# MIDImike.net
KiCad netlist of a schematic drawn in EAGLE
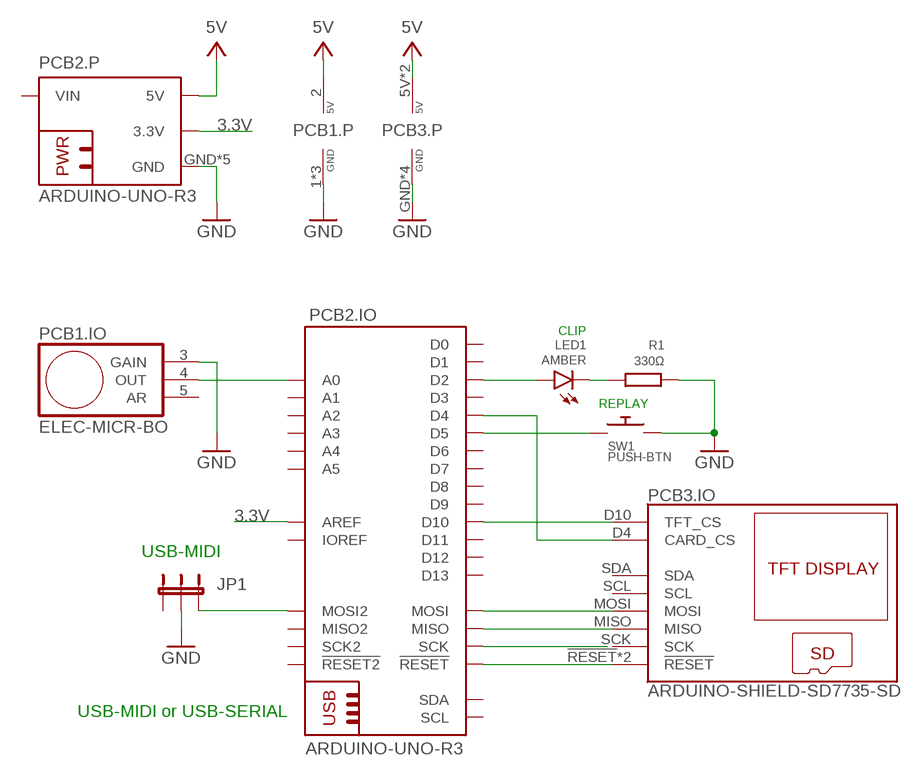
[diagram p0: schematic, sheet 1]

(export (version "E")
  (design (tool "Eeschema 10.0.6"))
  (components
    (comp (ref "JP1")
      (value "JP2E")
      (footprint "eagle-import:JP2")
      (libsource (lib "eagle-import") (part "JP2E"))
    )
    (comp (ref "LED1")
      (value "AMBER")
      (footprint "eagle-import:CHIPLED_0805")
      (libsource (lib "eagle-import") (part "LEDCHIPLED_0805"))
    )
    (comp (ref "PCB1")
      (value "ELEC-MICR-BO")
      (footprint "eagle-import:ELEC_MICR_BREAKOUT")
      (libsource (lib "eagle-import") (part "ELEC-MICR-BO"))
    )
    (comp (ref "PCB2")
      (value "ARDUINO-UNO-R3")
      (footprint "eagle-import:ARDUINO-UNO--R3")
      (libsource (lib "eagle-import") (part "ARDUINO-UNO-R3"))
    )
    (comp (ref "PCB3")
      (value "ARDUINO-SHIELD-SD7735-SD")
      (footprint "eagle-import:ARDIONO-SHIELD")
      (libsource (lib "eagle-import") (part "ARDUINO-SHIELD-SD7735-SD"))
    )
    (comp (ref "R1")
      (value "330Ω")
      (footprint "eagle-import:R0805")
      (fields (field (name "MANF") "Bourns"))
      (libsource (lib "eagle-import") (part "R-EU_R0805"))
    )
    (comp (ref "SW1")
      (value "PUSH-BTN")
      (footprint "eagle-import:TE_1-1825910-4")
      (fields
        (field (name "COMMENT") "1-1825910-4")
        (field (name "DIGI-KEY_PART_NUMBER") "450-1653-ND")
        (field (name "MF") "TE Connectivity")
      )
      (libsource (lib "eagle-import") (part "PUSH-BTN"))
    )
  )
  (nets
    (net (code "1") (name "/3.3V") (class "Default")
      (node (ref "PCB2") (pin "3.3V") (pinfunction "3.3V_3.3V") (pintype "power_in"))
      (node (ref "PCB2") (pin "AREF") (pinfunction "AREF_AREF") (pintype "bidirectional"))
    )
    (net (code "2") (name "/VIN") (class "Default")
      (node (ref "PCB2") (pin "VIN") (pinfunction "VIN_VIN") (pintype "power_in"))
    )
    (net (code "3") (name "5V") (class "Default")
      (node (ref "PCB1") (pin "2") (pinfunction "5V_2") (pintype "passive"))
      (node (ref "PCB2") (pin "5V") (pinfunction "5V_5V") (pintype "power_in"))
      (node (ref "PCB2") (pin "5V@1") (pinfunction "5V_5V@1") (pintype "power_in"))
      (node (ref "PCB2") (pin "5V@2") (pinfunction "5V_5V@2") (pintype "power_in"))
      (node (ref "PCB3") (pin "5V") (pinfunction "5V_5V") (pintype "passive"))
      (node (ref "PCB3") (pin "5V@1") (pinfunction "5V_5V@1") (pintype "passive"))
    )
    (net (code "4") (name "GND") (class "Default")
      (node (ref "JP1") (pin "2") (pinfunction "2_2") (pintype "passive"))
      (node (ref "PCB1") (pin "1") (pinfunction "GND_1") (pintype "power_in"))
      (node (ref "PCB1") (pin "3") (pinfunction "GAIN_3") (pintype "input"))
      (node (ref "PCB1") (pin "P$1") (pinfunction "GND_P$1") (pintype "power_in"))
      (node (ref "PCB1") (pin "P$2") (pinfunction "GND_P$2") (pintype "power_in"))
      (node (ref "PCB2") (pin "GND") (pinfunction "GND_GND") (pintype "power_in"))
      (node (ref "PCB2") (pin "GND@1") (pinfunction "GND_GND@1") (pintype "power_in"))
      (node (ref "PCB2") (pin "GND@2") (pinfunction "GND_GND@2") (pintype "power_in"))
      (node (ref "PCB2") (pin "GND@3") (pinfunction "GND_GND@3") (pintype "power_in"))
      (node (ref "PCB2") (pin "GND@4") (pinfunction "GND_GND@4") (pintype "power_in"))
      (node (ref "PCB3") (pin "GND") (pinfunction "GND_GND") (pintype "power_in"))
      (node (ref "PCB3") (pin "GND@1") (pinfunction "GND_GND@1") (pintype "power_in"))
      (node (ref "PCB3") (pin "GND@2") (pinfunction "GND_GND@2") (pintype "power_in"))
      (node (ref "PCB3") (pin "GND@3") (pinfunction "GND_GND@3") (pintype "power_in"))
      (node (ref "R1") (pin "1") (pinfunction "1_1") (pintype "passive"))
      (node (ref "SW1") (pin "2") (pinfunction "2_2") (pintype "passive"))
      (node (ref "SW1") (pin "2@1") (pinfunction "2_2@1") (pintype "passive"))
    )
    (net (code "5") (name "Net-(JP1-Pad3)") (class "Default")
      (node (ref "JP1") (pin "3") (pinfunction "3_3") (pintype "passive"))
      (node (ref "PCB2") (pin "MOSI2") (pinfunction "MOSI2_MOSI2") (pintype "bidirectional"))
    )
    (net (code "6") (name "Net-(LED1-PadA)") (class "Default")
      (node (ref "LED1") (pin "A") (pinfunction "A_A") (pintype "passive"))
      (node (ref "PCB2") (pin "D2") (pinfunction "D2_D2") (pintype "bidirectional"))
    )
    (net (code "7") (name "Net-(LED1-PadC)") (class "Default")
      (node (ref "LED1") (pin "C") (pinfunction "C_C") (pintype "passive"))
      (node (ref "R1") (pin "2") (pinfunction "2_2") (pintype "passive"))
    )
    (net (code "8") (name "Net-(PCB1A-OUT)") (class "Default")
      (node (ref "PCB1") (pin "4") (pinfunction "OUT_4") (pintype "output"))
      (node (ref "PCB2") (pin "A0") (pinfunction "A0_A0") (pintype "bidirectional"))
    )
    (net (code "9") (name "Net-(PCB2-PadD5)") (class "Default")
      (node (ref "PCB2") (pin "D5") (pinfunction "D5_D5") (pintype "bidirectional"))
      (node (ref "SW1") (pin "1") (pinfunction "1_1") (pintype "passive"))
      (node (ref "SW1") (pin "1@1") (pinfunction "1_1@1") (pintype "passive"))
    )
    (net (code "10") (name "Net-(PCB2-PadMISO)") (class "Default")
      (node (ref "PCB2") (pin "MISO") (pinfunction "MISO_MISO") (pintype "bidirectional"))
      (node (ref "PCB3") (pin "MISO") (pinfunction "MISO_MISO") (pintype "output"))
    )
    (net (code "11") (name "Net-(PCB2-PadMOSI)") (class "Default")
      (node (ref "PCB2") (pin "MOSI") (pinfunction "MOSI_MOSI") (pintype "bidirectional"))
      (node (ref "PCB3") (pin "MOSI") (pinfunction "MOSI_MOSI") (pintype "input"))
    )
    (net (code "12") (name "Net-(PCB2A-~{RESET}-Pad!RESET!)") (class "Default")
      (node (ref "PCB2") (pin "!RESET!") (pinfunction "~{RESET}_!RESET!") (pintype "bidirectional"))
      (node (ref "PCB2") (pin "!RESET!@1") (pinfunction "~{RESET}_!RESET!@1") (pintype "bidirectional"))
      (node (ref "PCB3") (pin "!RESET!") (pinfunction "~{RESET}_!RESET!") (pintype "bidirectional"))
      (node (ref "PCB3") (pin "!RESET!@1") (pinfunction "~{RESET}_!RESET!@1") (pintype "bidirectional"))
    )
    (net (code "13") (name "Net-(PCB3A-CARD_CS)") (class "Default")
      (node (ref "PCB2") (pin "D4") (pinfunction "D4_D4") (pintype "bidirectional"))
      (node (ref "PCB3") (pin "D4") (pinfunction "CARD_CS_D4") (pintype "input"))
    )
    (net (code "14") (name "Net-(PCB3A-TFT_CS)") (class "Default")
      (node (ref "PCB2") (pin "D10") (pinfunction "D10_D10") (pintype "bidirectional"))
      (node (ref "PCB3") (pin "D10") (pinfunction "TFT_CS_D10") (pintype "input"))
    )
    (net (code "15") (name "unconnected-(JP1-Pad1)") (class "Default")
      (node (ref "JP1") (pin "1") (pinfunction "1_1") (pintype "passive"))
    )
    (net (code "16") (name "unconnected-(PCB1A-AR-Pad5)") (class "Default")
      (node (ref "PCB1") (pin "5") (pinfunction "AR_5") (pintype "input"))
    )
    (net (code "17") (name "unconnected-(PCB2-PadA1)") (class "Default")
      (node (ref "PCB2") (pin "A1") (pinfunction "A1_A1") (pintype "bidirectional"))
    )
    (net (code "18") (name "unconnected-(PCB2-PadA2)") (class "Default")
      (node (ref "PCB2") (pin "A2") (pinfunction "A2_A2") (pintype "bidirectional"))
    )
    (net (code "19") (name "unconnected-(PCB2-PadA3)") (class "Default")
      (node (ref "PCB2") (pin "A3") (pinfunction "A3_A3") (pintype "bidirectional"))
    )
    (net (code "20") (name "unconnected-(PCB2-PadA4)") (class "Default")
      (node (ref "PCB2") (pin "A4") (pinfunction "A4_A4") (pintype "bidirectional"))
    )
    (net (code "21") (name "unconnected-(PCB2-PadA5)") (class "Default")
      (node (ref "PCB2") (pin "A5") (pinfunction "A5_A5") (pintype "bidirectional"))
    )
    (net (code "22") (name "unconnected-(PCB2-PadD0)") (class "Default")
      (node (ref "PCB2") (pin "D0") (pinfunction "D0_D0") (pintype "bidirectional"))
    )
    (net (code "23") (name "unconnected-(PCB2-PadD1)") (class "Default")
      (node (ref "PCB2") (pin "D1") (pinfunction "D1_D1") (pintype "bidirectional"))
    )
    (net (code "24") (name "unconnected-(PCB2-PadD3)") (class "Default")
      (node (ref "PCB2") (pin "D3") (pinfunction "D3_D3") (pintype "bidirectional"))
    )
    (net (code "25") (name "unconnected-(PCB2-PadD6)") (class "Default")
      (node (ref "PCB2") (pin "D6") (pinfunction "D6_D6") (pintype "bidirectional"))
    )
    (net (code "26") (name "unconnected-(PCB2-PadD7)") (class "Default")
      (node (ref "PCB2") (pin "D7") (pinfunction "D7_D7") (pintype "bidirectional"))
    )
    (net (code "27") (name "unconnected-(PCB2-PadD8)") (class "Default")
      (node (ref "PCB2") (pin "D8") (pinfunction "D8_D8") (pintype "bidirectional"))
    )
    (net (code "28") (name "unconnected-(PCB2-PadD9)") (class "Default")
      (node (ref "PCB2") (pin "D9") (pinfunction "D9_D9") (pintype "bidirectional"))
    )
    (net (code "29") (name "unconnected-(PCB2-PadD11)") (class "Default")
      (node (ref "PCB2") (pin "D11") (pinfunction "D11_D11") (pintype "bidirectional"))
    )
    (net (code "30") (name "unconnected-(PCB2-PadD12)") (class "Default")
      (node (ref "PCB2") (pin "D12") (pinfunction "D12_D12") (pintype "bidirectional"))
    )
    (net (code "31") (name "unconnected-(PCB2-PadD13)") (class "Default")
      (node (ref "PCB2") (pin "D13") (pinfunction "D13_D13") (pintype "bidirectional"))
    )
    (net (code "32") (name "unconnected-(PCB2-PadIOREF)") (class "Default")
      (node (ref "PCB2") (pin "IOREF") (pinfunction "IOREF_IOREF") (pintype "bidirectional"))
    )
    (net (code "33") (name "unconnected-(PCB2-PadMISO2)") (class "Default")
      (node (ref "PCB2") (pin "MISO2") (pinfunction "MISO2_MISO2") (pintype "bidirectional"))
    )
    (net (code "34") (name "unconnected-(PCB2-PadSCK)") (class "Default")
      (node (ref "PCB2") (pin "SCK") (pinfunction "SCK_SCK") (pintype "bidirectional"))
    )
    (net (code "35") (name "unconnected-(PCB2-PadSCK2)") (class "Default")
      (node (ref "PCB2") (pin "SCK2") (pinfunction "SCK2_SCK2") (pintype "bidirectional"))
    )
    (net (code "36") (name "unconnected-(PCB2-PadSCL)") (class "Default")
      (node (ref "PCB2") (pin "SCL") (pinfunction "SCL_SCL") (pintype "bidirectional"))
    )
    (net (code "37") (name "unconnected-(PCB2-PadSDA)") (class "Default")
      (node (ref "PCB2") (pin "SDA") (pinfunction "SDA_SDA") (pintype "bidirectional"))
    )
    (net (code "38") (name "unconnected-(PCB2A-~{RESET2}-Pad!RESET2!)") (class "Default")
      (node (ref "PCB2") (pin "!RESET2!") (pinfunction "~{RESET2}_!RESET2!") (pintype "bidirectional"))
    )
    (net (code "39") (name "unconnected-(PCB3-PadSCK)") (class "Default")
      (node (ref "PCB3") (pin "SCK") (pinfunction "SCK_SCK") (pintype "input"))
    )
    (net (code "40") (name "unconnected-(PCB3-PadSCL)") (class "Default")
      (node (ref "PCB3") (pin "SCL") (pinfunction "SCL_SCL") (pintype "input"))
    )
    (net (code "41") (name "unconnected-(PCB3-PadSDA)") (class "Default")
      (node (ref "PCB3") (pin "SDA") (pinfunction "SDA_SDA") (pintype "bidirectional"))
    )
  )
)
